# pcbLab.net
KiCad netlist of a schematic drawn in Altium Designer
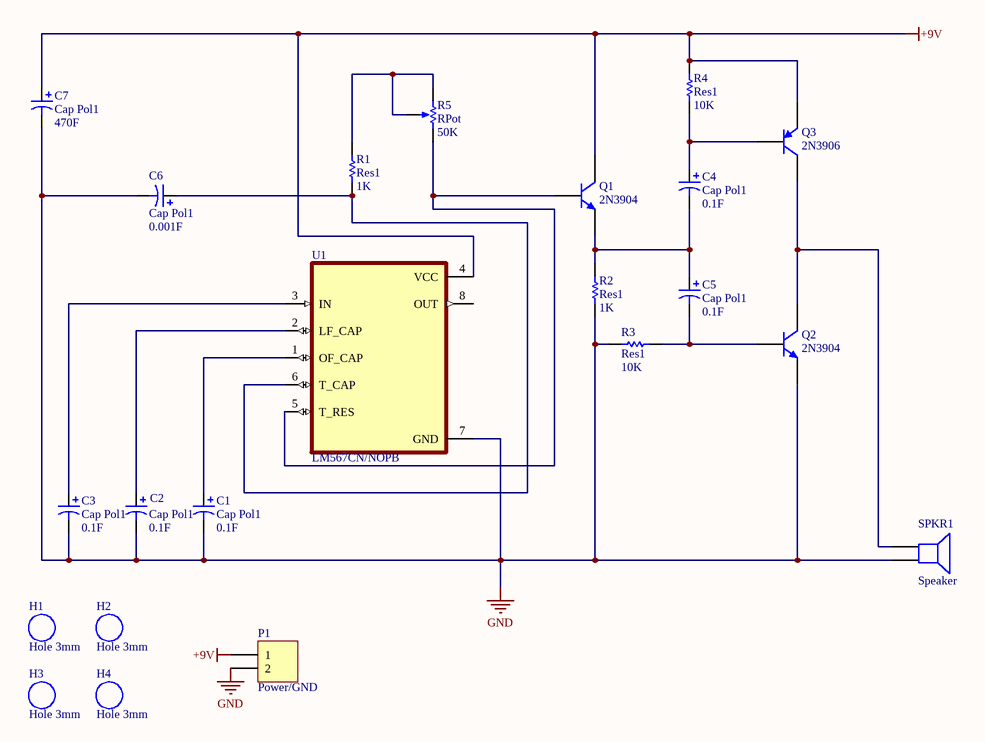
[diagram p0: pcbLab.SchDoc]

(export (version "E")
  (design (tool "Eeschema 10.0.6"))
  (components
    (comp (ref "C1")
      (value "Cap Pol1")
      (footprint "RAD-0.3")
      (description "Polarized Capacitor (Radial)")
      (fields (field (name "ALTIUM_VALUE") "0.1F") (field (name "PUBLISHER") "Altium Limited"))
      (libsource (lib "Miscellaneous Devices") (part "Cap Pol1"))
    )
    (comp (ref "C2")
      (value "Cap Pol1")
      (footprint "RAD-0.3")
      (description "Polarized Capacitor (Radial)")
      (fields (field (name "ALTIUM_VALUE") "0.1F") (field (name "PUBLISHER") "Altium Limited"))
      (libsource (lib "Miscellaneous Devices") (part "Cap Pol1"))
    )
    (comp (ref "C3")
      (value "Cap Pol1")
      (footprint "RAD-0.3")
      (description "Polarized Capacitor (Radial)")
      (fields (field (name "ALTIUM_VALUE") "0.1F") (field (name "PUBLISHER") "Altium Limited"))
      (libsource (lib "Miscellaneous Devices") (part "Cap Pol1"))
    )
    (comp (ref "C4")
      (value "Cap Pol1")
      (footprint "RAD-0.3")
      (description "Polarized Capacitor (Radial)")
      (fields (field (name "ALTIUM_VALUE") "0.1F") (field (name "PUBLISHER") "Altium Limited"))
      (libsource (lib "Miscellaneous Devices") (part "Cap Pol1"))
    )
    (comp (ref "C5")
      (value "Cap Pol1")
      (footprint "RAD-0.3")
      (description "Polarized Capacitor (Radial)")
      (fields (field (name "ALTIUM_VALUE") "0.1F") (field (name "PUBLISHER") "Altium Limited"))
      (libsource (lib "Miscellaneous Devices") (part "Cap Pol1"))
    )
    (comp (ref "C6")
      (value "Cap Pol1")
      (footprint "RAD-0.3")
      (description "Polarized Capacitor (Radial)")
      (fields (field (name "ALTIUM_VALUE") "0.001F") (field (name "PUBLISHER") "Altium Limited"))
      (libsource (lib "Miscellaneous Devices") (part "Cap Pol1"))
    )
    (comp (ref "C7")
      (value "Cap Pol1")
      (footprint "RAD-0.3")
      (description "Polarized Capacitor (Radial)")
      (fields (field (name "ALTIUM_VALUE") "470F") (field (name "PUBLISHER") "Altium Limited"))
      (libsource (lib "Miscellaneous Devices") (part "Cap Pol1"))
    )
    (comp (ref "H1")
      (value "Hole 3mm")
      (footprint "Hole 3mm")
      (libsource (lib "ECE LIB 21") (part "Hole 3mm"))
    )
    (comp (ref "H2")
      (value "Hole 3mm")
      (footprint "Hole 3mm")
      (libsource (lib "ECE LIB 21") (part "Hole 3mm"))
    )
    (comp (ref "H3")
      (value "Hole 3mm")
      (footprint "Hole 3mm")
      (libsource (lib "ECE LIB 21") (part "Hole 3mm"))
    )
    (comp (ref "H4")
      (value "Hole 3mm")
      (footprint "Hole 3mm")
      (libsource (lib "ECE LIB 21") (part "Hole 3mm"))
    )
    (comp (ref "P1")
      (value "Power/GND")
      (footprint "HDR1X2")
      (description "Header, 2-Pin")
      (fields (field (name "PUBLISHER") "Altium Limited"))
      (libsource (lib "Miscellaneous Connectors") (part "Header 2"))
    )
    (comp (ref "Q1")
      (value "2N3904")
      (footprint "TO-92A")
      (description "NPN General Purpose Amplifier")
      (fields (field (name "PUBLISHER") "Altium Limited"))
      (libsource (lib "Miscellaneous Devices") (part "2N3904"))
    )
    (comp (ref "Q2")
      (value "2N3904")
      (footprint "TO-92A")
      (description "NPN General Purpose Amplifier")
      (fields (field (name "PUBLISHER") "Altium Limited"))
      (libsource (lib "Miscellaneous Devices") (part "2N3904"))
    )
    (comp (ref "Q3")
      (value "2N3906")
      (footprint "TO-92A")
      (description "PNP General Purpose Amplifier")
      (fields (field (name "PUBLISHER") "Altium Limited"))
      (libsource (lib "Miscellaneous Devices") (part "2N3906"))
    )
    (comp (ref "R1")
      (value "Res1")
      (footprint "AXIAL-0.3")
      (description "Resistor")
      (fields (field (name "ALTIUM_VALUE") "1K") (field (name "PUBLISHER") "Altium Limited"))
      (libsource (lib "Miscellaneous Devices") (part "Res1"))
    )
    (comp (ref "R2")
      (value "Res1")
      (footprint "AXIAL-0.3")
      (description "Resistor")
      (fields (field (name "ALTIUM_VALUE") "1K") (field (name "PUBLISHER") "Altium Limited"))
      (libsource (lib "Miscellaneous Devices") (part "Res1"))
    )
    (comp (ref "R3")
      (value "Res1")
      (footprint "AXIAL-0.3")
      (description "Resistor")
      (fields (field (name "ALTIUM_VALUE") "10K") (field (name "PUBLISHER") "Altium Limited"))
      (libsource (lib "Miscellaneous Devices") (part "Res1"))
    )
    (comp (ref "R4")
      (value "Res1")
      (footprint "AXIAL-0.3")
      (description "Resistor")
      (fields (field (name "ALTIUM_VALUE") "10K") (field (name "PUBLISHER") "Altium Limited"))
      (libsource (lib "Miscellaneous Devices") (part "Res1"))
    )
    (comp (ref "R5")
      (value "RPot")
      (footprint "VR5")
      (description "Potentiometer")
      (fields (field (name "ALTIUM_VALUE") "50K") (field (name "PUBLISHER") "Altium Limited"))
      (libsource (lib "Miscellaneous Devices") (part "RPot"))
    )
    (comp (ref "SPKR1")
      (value "Speaker")
      (footprint "PIN2")
      (description "Loudspeaker")
      (fields (field (name "PUBLISHER") "Altium Limited"))
      (libsource (lib "Miscellaneous Devices") (part "Speaker"))
    )
    (comp (ref "U1")
      (value "LM567CN/NOPB")
      (footprint "DIP794W45P254L959H508Q8")
      (description "Telecom IC Tone Decoder 8-PDIP")
      (fields (field (name "MP") "LM567CN") (field (name "MF") "Texas Instruments"))
      (libsource (lib "LM567CN_NOPB") (part "LM567CN/NOPB"))
    )
  )
  (nets
    (net (code "1") (name "+9V") (class "Default")
      (node (ref "C7") (pin "1") (pinfunction "1_1") (pintype "passive"))
      (node (ref "P1") (pin "1") (pinfunction "1_1") (pintype "passive"))
      (node (ref "Q1") (pin "3") (pinfunction "C_3") (pintype "passive"))
      (node (ref "Q3") (pin "1") (pinfunction "E_1") (pintype "passive"))
      (node (ref "R4") (pin "2") (pinfunction "2_2") (pintype "passive"))
      (node (ref "U1") (pin "4") (pinfunction "VCC_4") (pintype "power_in"))
    )
    (net (code "2") (name "GND") (class "Default")
      (node (ref "C1") (pin "2") (pinfunction "2_2") (pintype "passive"))
      (node (ref "C2") (pin "2") (pinfunction "2_2") (pintype "passive"))
      (node (ref "C3") (pin "2") (pinfunction "2_2") (pintype "passive"))
      (node (ref "C6") (pin "2") (pinfunction "2_2") (pintype "passive"))
      (node (ref "C7") (pin "2") (pinfunction "2_2") (pintype "passive"))
      (node (ref "P1") (pin "2") (pinfunction "2_2") (pintype "passive"))
      (node (ref "Q2") (pin "1") (pinfunction "E_1") (pintype "passive"))
      (node (ref "R2") (pin "2") (pinfunction "2_2") (pintype "passive"))
      (node (ref "R3") (pin "1") (pinfunction "1_1") (pintype "passive"))
      (node (ref "SPKR1") (pin "2") (pinfunction "2_2") (pintype "passive"))
      (node (ref "U1") (pin "7") (pinfunction "GND_7") (pintype "power_in"))
    )
    (net (code "3") (name "Net-(Q1-B)") (class "Default")
      (node (ref "Q1") (pin "2") (pinfunction "B_2") (pintype "passive"))
      (node (ref "R5") (pin "2") (pinfunction "BOT_2") (pintype "passive"))
      (node (ref "U1") (pin "5") (pinfunction "T_RES_5") (pintype "bidirectional"))
    )
    (net (code "4") (name "Net-(Q1-E)") (class "Default")
      (node (ref "C4") (pin "2") (pinfunction "2_2") (pintype "passive"))
      (node (ref "C5") (pin "1") (pinfunction "1_1") (pintype "passive"))
      (node (ref "Q1") (pin "1") (pinfunction "E_1") (pintype "passive"))
      (node (ref "R2") (pin "1") (pinfunction "1_1") (pintype "passive"))
    )
    (net (code "5") (name "Net-(Q2-B)") (class "Default")
      (node (ref "C5") (pin "2") (pinfunction "2_2") (pintype "passive"))
      (node (ref "Q2") (pin "2") (pinfunction "B_2") (pintype "passive"))
      (node (ref "R3") (pin "2") (pinfunction "2_2") (pintype "passive"))
    )
    (net (code "6") (name "Net-(Q2-C)") (class "Default")
      (node (ref "Q2") (pin "3") (pinfunction "C_3") (pintype "passive"))
      (node (ref "Q3") (pin "3") (pinfunction "C_3") (pintype "passive"))
      (node (ref "SPKR1") (pin "1") (pinfunction "1_1") (pintype "passive"))
    )
    (net (code "7") (name "Net-(Q3-B)") (class "Default")
      (node (ref "C4") (pin "1") (pinfunction "1_1") (pintype "passive"))
      (node (ref "Q3") (pin "2") (pinfunction "B_2") (pintype "passive"))
      (node (ref "R4") (pin "1") (pinfunction "1_1") (pintype "passive"))
    )
    (net (code "8") (name "Net-(R5-TAP)") (class "Default")
      (node (ref "R1") (pin "2") (pinfunction "2_2") (pintype "passive"))
      (node (ref "R5") (pin "1") (pinfunction "TOP_1") (pintype "passive"))
      (node (ref "R5") (pin "3") (pinfunction "TAP_3") (pintype "passive"))
    )
    (net (code "9") (name "Net-(U1-IN)") (class "Default")
      (node (ref "C3") (pin "1") (pinfunction "1_1") (pintype "passive"))
      (node (ref "U1") (pin "3") (pinfunction "IN_3") (pintype "input"))
    )
    (net (code "10") (name "Net-(U1-LF_CAP)") (class "Default")
      (node (ref "C2") (pin "1") (pinfunction "1_1") (pintype "passive"))
      (node (ref "U1") (pin "2") (pinfunction "LF_CAP_2") (pintype "bidirectional"))
    )
    (net (code "11") (name "Net-(U1-OF_CAP)") (class "Default")
      (node (ref "C1") (pin "1") (pinfunction "1_1") (pintype "passive"))
      (node (ref "U1") (pin "1") (pinfunction "OF_CAP_1") (pintype "bidirectional"))
    )
    (net (code "12") (name "Net-(U1-T_CAP)") (class "Default")
      (node (ref "C6") (pin "1") (pinfunction "1_1") (pintype "passive"))
      (node (ref "R1") (pin "1") (pinfunction "1_1") (pintype "passive"))
      (node (ref "U1") (pin "6") (pinfunction "T_CAP_6") (pintype "bidirectional"))
    )
    (net (code "13") (name "unconnected-(U1-OUT-Pad8)") (class "Default")
      (node (ref "U1") (pin "8") (pinfunction "OUT_8") (pintype "output"))
    )
  )
)
